# Charge.net
KiCad netlist of a schematic drawn in Altium Designer
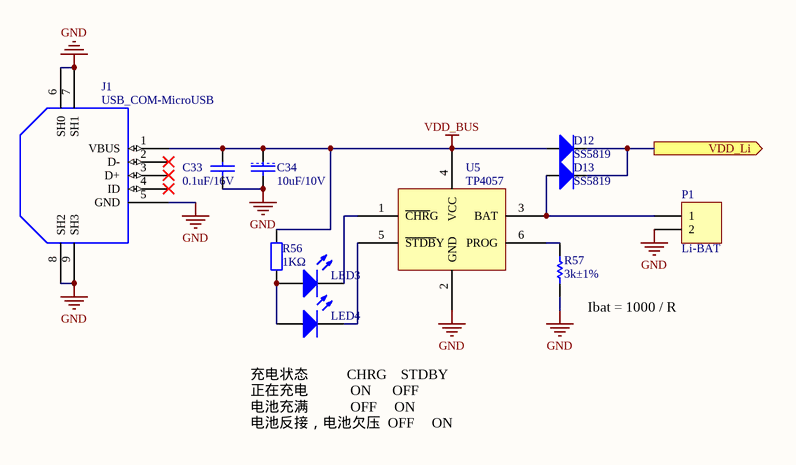
[diagram p0: Charge.SchDoc]

(export (version "E")
  (design (tool "Eeschema 10.0.6"))
  (components
    (comp (ref "C33")
      (value "0.1uF/16V")
      (footprint "0603R")
      (description "贴片陶瓷电容")
      (libsource (lib "*") (part "CAP"))
    )
    (comp (ref "C34")
      (value "10uF/10V")
      (footprint "0805R")
      (description "贴片陶瓷电容")
      (fields (field (name "AUTHOR") "叶建峰"))
      (libsource (lib "") (part "CAP_1"))
    )
    (comp (ref "D12")
      (value "SS5819")
      (footprint "SMA")
      (description "贴片二极管")
      (fields (field (name "AUTHOR") "叶建峰"))
      (libsource (lib "Miscellaneous Devices") (part "Diode 1N914"))
    )
    (comp (ref "D13")
      (value "SS5819")
      (footprint "SMA")
      (description "贴片二极管")
      (fields (field (name "AUTHOR") "叶建峰"))
      (libsource (lib "Miscellaneous Devices") (part "Diode 1N914"))
    )
    (comp (ref "J1")
      (value "USB_COM-MicroUSB")
      (footprint "USB_MINIB_SMT")
      (libsource (lib "RC-sheet") (part "USB_COM-MiniUSB"))
    )
    (comp (ref "LED3")
      (value "LED-0805")
      (footprint "LED-0603")
      (description "LED_0603 Typical RED, GREEN, YELLOW, AMBER GaAs LED")
      (libsource (lib "altium-import") (part "root_0_LED_0603_"))
    )
    (comp (ref "LED4")
      (value "LED-0805")
      (footprint "LED-0603")
      (description "LED_0603 Typical RED, GREEN, YELLOW, AMBER GaAs LED")
      (libsource (lib "altium-import") (part "root_0_LED_0603_"))
    )
    (comp (ref "P1")
      (value "Li-BAT")
      (footprint "CON2-2.0")
      (description "Header, 2-Pin")
      (fields (field (name "PUBLISHER") "Altium Limited"))
      (libsource (lib "Miscellaneous Connectors") (part "Header 2"))
    )
    (comp (ref "R56")
      (value "1KΩ")
      (footprint "0603R")
      (libsource (lib "altium-import") (part "root_3_RES_0603_"))
    )
    (comp (ref "R57")
      (value "3k±1%")
      (footprint "0603R")
      (description "贴片电阻")
      (libsource (lib "Miscellaneous Devices") (part "Res1"))
    )
    (comp (ref "U5")
      (value "TP4057")
      (footprint "SOT23-6")
      (description "锂电充电芯片")
      (fields (field (name "MANUFACTURER") "南京拓微集成电路") (field (name "AUTHOR") "叶建峰"))
      (libsource (lib "led") (part "TP4057"))
    )
  )
  (nets
    (net (code "1") (name "/VDD_Li") (class "Default")
      (node (ref "D12") (pin "2") (pinfunction "K_2") (pintype "passive"))
      (node (ref "D13") (pin "2") (pinfunction "K_2") (pintype "passive"))
    )
    (net (code "2") (name "GND") (class "Default")
      (node (ref "C33") (pin "2") (pinfunction "2_2") (pintype "passive"))
      (node (ref "C34") (pin "2") (pinfunction "2_2") (pintype "passive"))
      (node (ref "J1") (pin "5") (pinfunction "GND_5") (pintype "power_in"))
      (node (ref "J1") (pin "6") (pinfunction "SH0_6") (pintype "passive"))
      (node (ref "J1") (pin "7") (pinfunction "SH1_7") (pintype "passive"))
      (node (ref "J1") (pin "8") (pinfunction "SH2_8") (pintype "passive"))
      (node (ref "J1") (pin "9") (pinfunction "SH3_9") (pintype "passive"))
      (node (ref "P1") (pin "2") (pinfunction "2_2") (pintype "passive"))
      (node (ref "R57") (pin "1") (pinfunction "1_1") (pintype "passive"))
      (node (ref "U5") (pin "2") (pinfunction "GND_2") (pintype "passive"))
    )
    (net (code "3") (name "Net-(D13-A)") (class "Default")
      (node (ref "D13") (pin "1") (pinfunction "A_1") (pintype "passive"))
      (node (ref "P1") (pin "1") (pinfunction "1_1") (pintype "passive"))
      (node (ref "U5") (pin "3") (pinfunction "BAT_3") (pintype "passive"))
    )
    (net (code "4") (name "Net-(LED3-A)") (class "Default")
      (node (ref "LED3") (pin "1") (pinfunction "A_1") (pintype "passive"))
      (node (ref "LED4") (pin "1") (pinfunction "A_1") (pintype "passive"))
      (node (ref "R56") (pin "2") (pinfunction "2_2") (pintype "passive"))
    )
    (net (code "5") (name "Net-(LED3-K)") (class "Default")
      (node (ref "LED3") (pin "2") (pinfunction "K_2") (pintype "passive"))
      (node (ref "U5") (pin "1") (pinfunction "~{CHR}G_1") (pintype "passive"))
    )
    (net (code "6") (name "Net-(LED4-K)") (class "Default")
      (node (ref "LED4") (pin "2") (pinfunction "K_2") (pintype "passive"))
      (node (ref "U5") (pin "5") (pinfunction "~{STDB}Y_5") (pintype "passive"))
    )
    (net (code "7") (name "Net-(U5-PROG)") (class "Default")
      (node (ref "R57") (pin "2") (pinfunction "2_2") (pintype "passive"))
      (node (ref "U5") (pin "6") (pinfunction "PROG_6") (pintype "passive"))
    )
    (net (code "8") (name "VDD_BUS") (class "Default")
      (node (ref "C33") (pin "1") (pinfunction "1_1") (pintype "passive"))
      (node (ref "C34") (pin "1") (pinfunction "1_1") (pintype "passive"))
      (node (ref "D12") (pin "1") (pinfunction "A_1") (pintype "passive"))
      (node (ref "J1") (pin "1") (pinfunction "VBUS_1") (pintype "bidirectional"))
      (node (ref "R56") (pin "1") (pinfunction "1_1") (pintype "passive"))
      (node (ref "U5") (pin "4") (pinfunction "VCC_4") (pintype "passive"))
    )
    (net (code "9") (name "unconnected-(J1-D+-Pad3)") (class "Default")
      (node (ref "J1") (pin "3") (pinfunction "D+_3") (pintype "bidirectional+no_connect"))
    )
    (net (code "10") (name "unconnected-(J1-D--Pad2)") (class "Default")
      (node (ref "J1") (pin "2") (pinfunction "D-_2") (pintype "bidirectional+no_connect"))
    )
    (net (code "11") (name "unconnected-(J1-ID-Pad4)") (class "Default")
      (node (ref "J1") (pin "4") (pinfunction "ID_4") (pintype "bidirectional+no_connect"))
    )
  )
)
